# MTRduino_Rev2_1.net
KiCad netlist of a schematic drawn in EAGLE
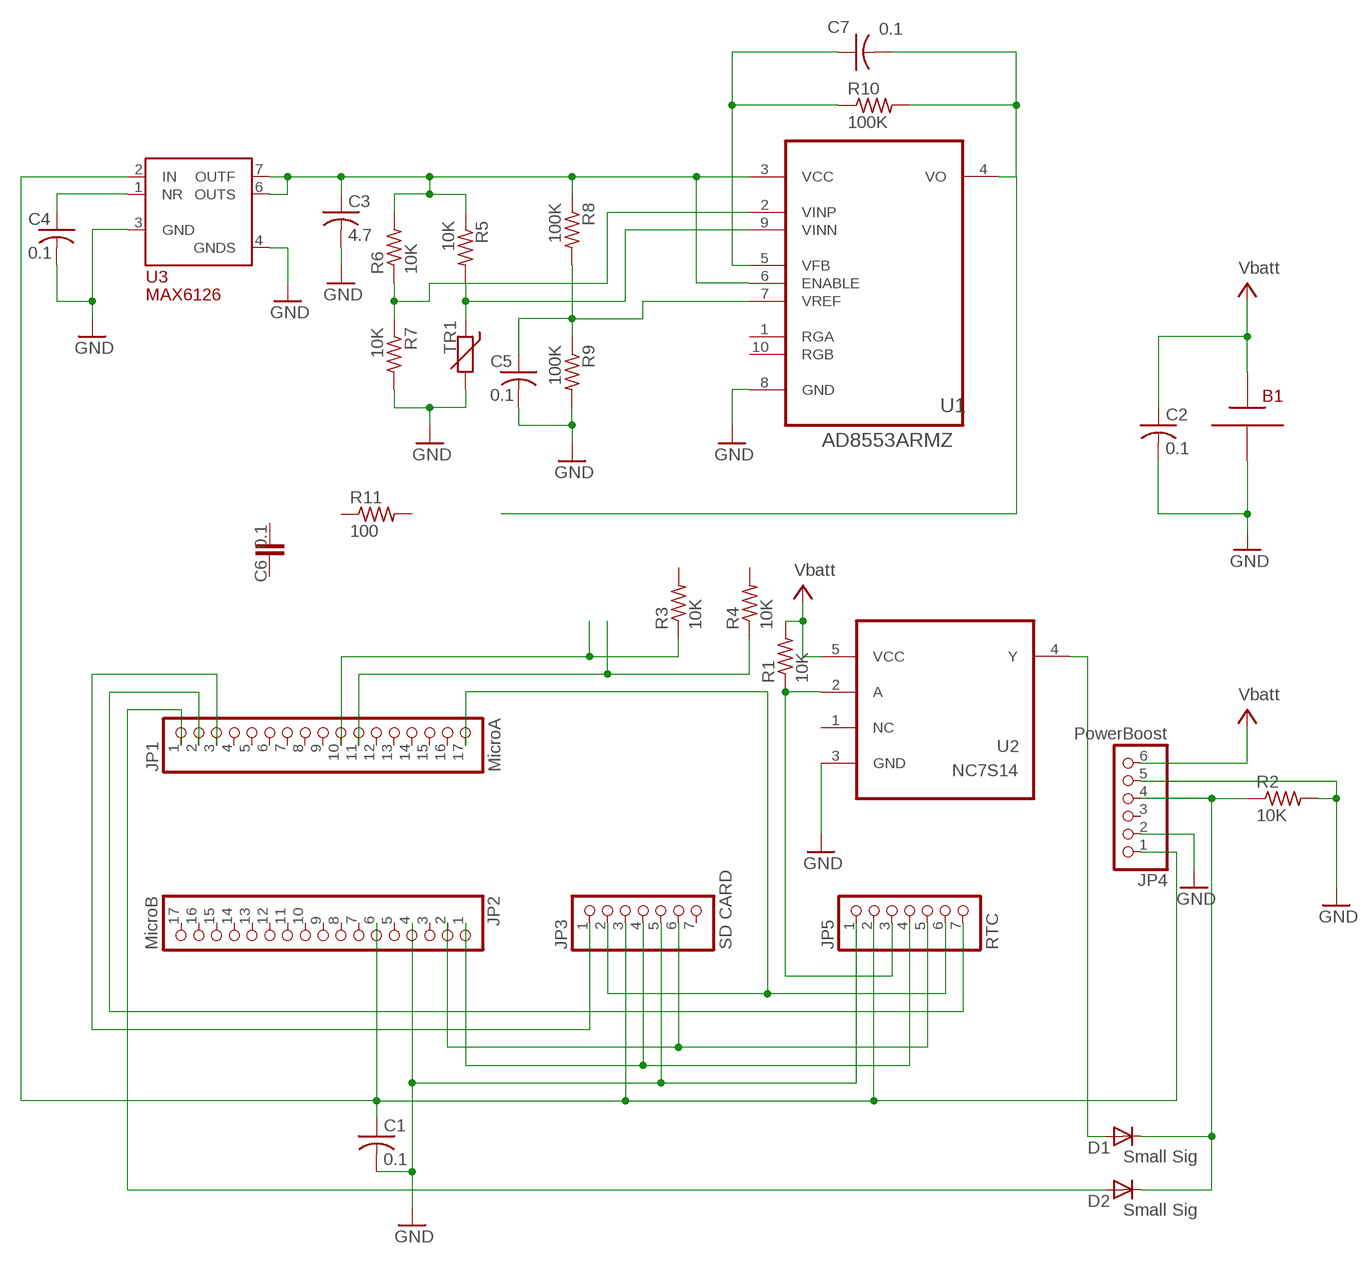
[diagram p0: schematic, sheet 1]

(export (version "E")
  (design (tool "Eeschema 10.0.6"))
  (components
    (comp (ref "B1")
      (value "2x AA BATT")
      (footprint "eagle-import:BATT_AA2")
      (libsource (lib "eagle-import") (part "BATT_AA2"))
    )
    (comp (ref "C1")
      (value "0.1")
      (footprint "eagle-import:C0603")
      (libsource (lib "eagle-import") (part "C-USC0603"))
    )
    (comp (ref "C2")
      (value "0.1")
      (footprint "eagle-import:C0603")
      (libsource (lib "eagle-import") (part "C-USC0603"))
    )
    (comp (ref "C3")
      (value "4.7")
      (footprint "eagle-import:C0603")
      (libsource (lib "eagle-import") (part "C-USC0603"))
    )
    (comp (ref "C4")
      (value "0.1")
      (footprint "eagle-import:C0603")
      (libsource (lib "eagle-import") (part "C-USC0603"))
    )
    (comp (ref "C5")
      (value "0.1")
      (footprint "eagle-import:C0603")
      (libsource (lib "eagle-import") (part "C-USC0603"))
    )
    (comp (ref "C6")
      (value "0.1")
      (footprint "eagle-import:C0603")
      (libsource (lib "eagle-import") (part "C-EUC0603"))
    )
    (comp (ref "C7")
      (value "0.1")
      (footprint "eagle-import:C0603")
      (libsource (lib "eagle-import") (part "C-USC0603"))
    )
    (comp (ref "D1")
      (value "Small Sig")
      (footprint "eagle-import:SOD-323F")
      (libsource (lib "eagle-import") (part "DIODESOD-323F"))
    )
    (comp (ref "D2")
      (value "Small Sig")
      (footprint "eagle-import:SOD-323F")
      (libsource (lib "eagle-import") (part "DIODESOD-323F"))
    )
    (comp (ref "JP1")
      (value "MicroA")
      (footprint "eagle-import:1X17")
      (libsource (lib "eagle-import") (part "PINHD-1X17"))
    )
    (comp (ref "JP2")
      (value "MicroB")
      (footprint "eagle-import:1X17")
      (libsource (lib "eagle-import") (part "PINHD-1X17"))
    )
    (comp (ref "JP3")
      (value "SD CARD")
      (footprint "eagle-import:1X07")
      (libsource (lib "eagle-import") (part "PINHD-1X7"))
    )
    (comp (ref "JP4")
      (value "PowerBoost")
      (footprint "eagle-import:1X06")
      (libsource (lib "eagle-import") (part "PINHD-1X6"))
    )
    (comp (ref "JP5")
      (value "RTC")
      (footprint "eagle-import:1X07")
      (libsource (lib "eagle-import") (part "PINHD-1X7"))
    )
    (comp (ref "R1")
      (value "10K")
      (footprint "eagle-import:R0603")
      (libsource (lib "eagle-import") (part "R-US_R0603"))
    )
    (comp (ref "R2")
      (value "10K")
      (footprint "eagle-import:R0603")
      (libsource (lib "eagle-import") (part "R-US_R0603"))
    )
    (comp (ref "R3")
      (value "10K")
      (footprint "eagle-import:R0603")
      (libsource (lib "eagle-import") (part "R-US_R0603"))
    )
    (comp (ref "R4")
      (value "10K")
      (footprint "eagle-import:R0603")
      (libsource (lib "eagle-import") (part "R-US_R0603"))
    )
    (comp (ref "R5")
      (value "10K")
      (footprint "eagle-import:R0603")
      (libsource (lib "eagle-import") (part "R-US_R0603"))
    )
    (comp (ref "R6")
      (value "10K")
      (footprint "eagle-import:R0603")
      (libsource (lib "eagle-import") (part "R-US_R0603"))
    )
    (comp (ref "R7")
      (value "10K")
      (footprint "eagle-import:R0603")
      (libsource (lib "eagle-import") (part "R-US_R0603"))
    )
    (comp (ref "R8")
      (value "100K")
      (footprint "eagle-import:R0603")
      (libsource (lib "eagle-import") (part "R-US_R0603"))
    )
    (comp (ref "R9")
      (value "100K")
      (footprint "eagle-import:R0603")
      (libsource (lib "eagle-import") (part "R-US_R0603"))
    )
    (comp (ref "R10")
      (value "100K")
      (footprint "eagle-import:R0603")
      (libsource (lib "eagle-import") (part "R-US_R0603"))
    )
    (comp (ref "R11")
      (value "100")
      (footprint "eagle-import:R0603")
      (libsource (lib "eagle-import") (part "R-US_R0603"))
    )
    (comp (ref "TR1")
      (value "10K")
      (footprint "eagle-import:R-5")
      (libsource (lib "eagle-import") (part "THERMISTOR_R-5"))
    )
    (comp (ref "U1")
      (value "AD8553ARMZ")
      (footprint "eagle-import:SOP50P490X110-10N")
      (libsource (lib "eagle-import") (part "AD8553ARMZ"))
    )
    (comp (ref "U2")
      (value "NC7S14")
      (footprint "eagle-import:SOT95P280X145-5N")
      (fields (field (name "MPN") "1P1G14MDBVREPG4"))
      (libsource (lib "eagle-import") (part "1P1G14MDBVREPG4"))
    )
    (comp (ref "U3")
      (value "MAX6126")
      (footprint "eagle-import:SOIC127P600X175-8N")
      (libsource (lib "eagle-import") (part "MAX6126"))
    )
  )
  (nets
    (net (code "1") (name "GND") (class "Default")
      (node (ref "B1") (pin "-") (pinfunction "-_-") (pintype "bidirectional"))
      (node (ref "C1") (pin "2") (pinfunction "2_2") (pintype "passive"))
      (node (ref "C2") (pin "2") (pinfunction "2_2") (pintype "passive"))
      (node (ref "C3") (pin "2") (pinfunction "2_2") (pintype "passive"))
      (node (ref "C4") (pin "2") (pinfunction "2_2") (pintype "passive"))
      (node (ref "C5") (pin "2") (pinfunction "2_2") (pintype "passive"))
      (node (ref "JP2") (pin "4") (pinfunction "4_4") (pintype "passive"))
      (node (ref "JP3") (pin "5") (pinfunction "5_5") (pintype "passive"))
      (node (ref "JP4") (pin "2") (pinfunction "2_2") (pintype "passive"))
      (node (ref "JP4") (pin "5") (pinfunction "5_5") (pintype "passive"))
      (node (ref "JP5") (pin "1") (pinfunction "1_1") (pintype "passive"))
      (node (ref "R2") (pin "2") (pinfunction "2_2") (pintype "passive"))
      (node (ref "R7") (pin "2") (pinfunction "2_2") (pintype "passive"))
      (node (ref "R9") (pin "2") (pinfunction "2_2") (pintype "passive"))
      (node (ref "TR1") (pin "2") (pinfunction "2_2") (pintype "passive"))
      (node (ref "U1") (pin "8") (pinfunction "GND_8") (pintype "passive"))
      (node (ref "U2") (pin "3") (pinfunction "GND_3") (pintype "passive"))
      (node (ref "U3") (pin "3") (pinfunction "GND_3") (pintype "input"))
      (node (ref "U3") (pin "4") (pinfunction "GNDS_4") (pintype "input"))
    )
    (net (code "2") (name "Net-(D1-PadC)") (class "Default")
      (node (ref "D1") (pin "C") (pinfunction "C_C") (pintype "passive"))
      (node (ref "D2") (pin "C") (pinfunction "C_C") (pintype "passive"))
      (node (ref "JP4") (pin "4") (pinfunction "4_4") (pintype "passive"))
      (node (ref "R2") (pin "1") (pinfunction "1_1") (pintype "passive"))
    )
    (net (code "3") (name "Net-(D2-PadA)") (class "Default")
      (node (ref "D2") (pin "A") (pinfunction "A_A") (pintype "passive"))
      (node (ref "JP1") (pin "1") (pinfunction "1_1") (pintype "passive"))
    )
    (net (code "4") (name "Net-(JP1-Pad2)") (class "Default")
      (node (ref "JP1") (pin "2") (pinfunction "2_2") (pintype "passive"))
      (node (ref "JP5") (pin "7") (pinfunction "7_7") (pintype "passive"))
    )
    (net (code "5") (name "Net-(JP1-Pad3)") (class "Default")
      (node (ref "JP1") (pin "3") (pinfunction "3_3") (pintype "passive"))
      (node (ref "JP3") (pin "1") (pinfunction "1_1") (pintype "passive"))
    )
    (net (code "6") (name "Net-(JP1-Pad10)") (class "Default")
      (node (ref "JP1") (pin "10") (pinfunction "10_10") (pintype "passive"))
      (node (ref "R3") (pin "1") (pinfunction "1_1") (pintype "passive"))
    )
    (net (code "7") (name "Net-(JP1-Pad11)") (class "Default")
      (node (ref "JP1") (pin "11") (pinfunction "11_11") (pintype "passive"))
      (node (ref "R4") (pin "1") (pinfunction "1_1") (pintype "passive"))
    )
    (net (code "8") (name "Net-(JP1-Pad17)") (class "Default")
      (node (ref "JP1") (pin "17") (pinfunction "17_17") (pintype "passive"))
      (node (ref "JP3") (pin "2") (pinfunction "2_2") (pintype "passive"))
      (node (ref "JP5") (pin "6") (pinfunction "6_6") (pintype "passive"))
    )
    (net (code "9") (name "Net-(JP2-Pad1)") (class "Default")
      (node (ref "JP2") (pin "1") (pinfunction "1_1") (pintype "passive"))
      (node (ref "JP3") (pin "4") (pinfunction "4_4") (pintype "passive"))
      (node (ref "JP5") (pin "4") (pinfunction "4_4") (pintype "passive"))
    )
    (net (code "10") (name "Net-(JP2-Pad2)") (class "Default")
      (node (ref "JP2") (pin "2") (pinfunction "2_2") (pintype "passive"))
      (node (ref "JP3") (pin "6") (pinfunction "6_6") (pintype "passive"))
      (node (ref "JP5") (pin "5") (pinfunction "5_5") (pintype "passive"))
    )
    (net (code "11") (name "Net-(U1-ENABLE)") (class "Default")
      (node (ref "C3") (pin "1") (pinfunction "1_1") (pintype "passive"))
      (node (ref "R5") (pin "1") (pinfunction "1_1") (pintype "passive"))
      (node (ref "R6") (pin "2") (pinfunction "2_2") (pintype "passive"))
      (node (ref "R8") (pin "1") (pinfunction "1_1") (pintype "passive"))
      (node (ref "U1") (pin "3") (pinfunction "VCC_3") (pintype "power_in"))
      (node (ref "U1") (pin "6") (pinfunction "ENABLE_6") (pintype "input"))
      (node (ref "U3") (pin "6") (pinfunction "OUTS_6") (pintype "output"))
      (node (ref "U3") (pin "7") (pinfunction "OUTF_7") (pintype "output"))
    )
    (net (code "12") (name "Net-(U1-VFB)") (class "Default")
      (node (ref "C7") (pin "1") (pinfunction "1_1") (pintype "passive"))
      (node (ref "R10") (pin "1") (pinfunction "1_1") (pintype "passive"))
      (node (ref "U1") (pin "5") (pinfunction "VFB_5") (pintype "input"))
    )
    (net (code "13") (name "Net-(U1-VINN)") (class "Default")
      (node (ref "R5") (pin "2") (pinfunction "2_2") (pintype "passive"))
      (node (ref "TR1") (pin "1") (pinfunction "1_1") (pintype "passive"))
      (node (ref "U1") (pin "9") (pinfunction "VINN_9") (pintype "input"))
    )
    (net (code "14") (name "Net-(U1-VINP)") (class "Default")
      (node (ref "R6") (pin "1") (pinfunction "1_1") (pintype "passive"))
      (node (ref "R7") (pin "1") (pinfunction "1_1") (pintype "passive"))
      (node (ref "U1") (pin "2") (pinfunction "VINP_2") (pintype "input"))
    )
    (net (code "15") (name "Net-(U1-VO)") (class "Default")
      (node (ref "C7") (pin "2") (pinfunction "2_2") (pintype "passive"))
      (node (ref "R10") (pin "2") (pinfunction "2_2") (pintype "passive"))
      (node (ref "U1") (pin "4") (pinfunction "VO_4") (pintype "output"))
    )
    (net (code "16") (name "Net-(U1-VREF)") (class "Default")
      (node (ref "C5") (pin "1") (pinfunction "1_1") (pintype "passive"))
      (node (ref "R8") (pin "2") (pinfunction "2_2") (pintype "passive"))
      (node (ref "R9") (pin "1") (pinfunction "1_1") (pintype "passive"))
      (node (ref "U1") (pin "7") (pinfunction "VREF_7") (pintype "input"))
    )
    (net (code "17") (name "Net-(U2-A)") (class "Default")
      (node (ref "JP5") (pin "3") (pinfunction "3_3") (pintype "passive"))
      (node (ref "R1") (pin "1") (pinfunction "1_1") (pintype "passive"))
      (node (ref "U2") (pin "2") (pinfunction "A_2") (pintype "input"))
    )
    (net (code "18") (name "Net-(U2-Y)") (class "Default")
      (node (ref "D1") (pin "A") (pinfunction "A_A") (pintype "passive"))
      (node (ref "U2") (pin "4") (pinfunction "Y_4") (pintype "output"))
    )
    (net (code "19") (name "Net-(U3-IN)") (class "Default")
      (node (ref "C1") (pin "1") (pinfunction "1_1") (pintype "passive"))
      (node (ref "JP2") (pin "6") (pinfunction "6_6") (pintype "passive"))
      (node (ref "JP3") (pin "3") (pinfunction "3_3") (pintype "passive"))
      (node (ref "JP4") (pin "1") (pinfunction "1_1") (pintype "passive"))
      (node (ref "JP5") (pin "2") (pinfunction "2_2") (pintype "passive"))
      (node (ref "U3") (pin "2") (pinfunction "IN_2") (pintype "input"))
    )
    (net (code "20") (name "Net-(U3-NR)") (class "Default")
      (node (ref "C4") (pin "1") (pinfunction "1_1") (pintype "passive"))
      (node (ref "U3") (pin "1") (pinfunction "NR_1") (pintype "bidirectional"))
    )
    (net (code "21") (name "Vbatt") (class "Default")
      (node (ref "B1") (pin "+") (pinfunction "+_+") (pintype "bidirectional"))
      (node (ref "C2") (pin "1") (pinfunction "1_1") (pintype "passive"))
      (node (ref "JP4") (pin "6") (pinfunction "6_6") (pintype "passive"))
      (node (ref "R1") (pin "2") (pinfunction "2_2") (pintype "passive"))
      (node (ref "U2") (pin "5") (pinfunction "VCC_5") (pintype "power_in"))
    )
    (net (code "22") (name "unconnected-(C6-Pad1)") (class "Default")
      (node (ref "C6") (pin "1") (pinfunction "1_1") (pintype "passive"))
    )
    (net (code "23") (name "unconnected-(C6-Pad2)") (class "Default")
      (node (ref "C6") (pin "2") (pinfunction "2_2") (pintype "passive"))
    )
    (net (code "24") (name "unconnected-(JP1-Pad4)") (class "Default")
      (node (ref "JP1") (pin "4") (pinfunction "4_4") (pintype "passive"))
    )
    (net (code "25") (name "unconnected-(JP1-Pad5)") (class "Default")
      (node (ref "JP1") (pin "5") (pinfunction "5_5") (pintype "passive"))
    )
    (net (code "26") (name "unconnected-(JP1-Pad6)") (class "Default")
      (node (ref "JP1") (pin "6") (pinfunction "6_6") (pintype "passive"))
    )
    (net (code "27") (name "unconnected-(JP1-Pad7)") (class "Default")
      (node (ref "JP1") (pin "7") (pinfunction "7_7") (pintype "passive"))
    )
    (net (code "28") (name "unconnected-(JP1-Pad8)") (class "Default")
      (node (ref "JP1") (pin "8") (pinfunction "8_8") (pintype "passive"))
    )
    (net (code "29") (name "unconnected-(JP1-Pad9)") (class "Default")
      (node (ref "JP1") (pin "9") (pinfunction "9_9") (pintype "passive"))
    )
    (net (code "30") (name "unconnected-(JP1-Pad12)") (class "Default")
      (node (ref "JP1") (pin "12") (pinfunction "12_12") (pintype "passive"))
    )
    (net (code "31") (name "unconnected-(JP1-Pad13)") (class "Default")
      (node (ref "JP1") (pin "13") (pinfunction "13_13") (pintype "passive"))
    )
    (net (code "32") (name "unconnected-(JP1-Pad14)") (class "Default")
      (node (ref "JP1") (pin "14") (pinfunction "14_14") (pintype "passive"))
    )
    (net (code "33") (name "unconnected-(JP1-Pad15)") (class "Default")
      (node (ref "JP1") (pin "15") (pinfunction "15_15") (pintype "passive"))
    )
    (net (code "34") (name "unconnected-(JP1-Pad16)") (class "Default")
      (node (ref "JP1") (pin "16") (pinfunction "16_16") (pintype "passive"))
    )
    (net (code "35") (name "unconnected-(JP2-Pad3)") (class "Default")
      (node (ref "JP2") (pin "3") (pinfunction "3_3") (pintype "passive"))
    )
    (net (code "36") (name "unconnected-(JP2-Pad5)") (class "Default")
      (node (ref "JP2") (pin "5") (pinfunction "5_5") (pintype "passive"))
    )
    (net (code "37") (name "unconnected-(JP2-Pad7)") (class "Default")
      (node (ref "JP2") (pin "7") (pinfunction "7_7") (pintype "passive"))
    )
    (net (code "38") (name "unconnected-(JP2-Pad8)") (class "Default")
      (node (ref "JP2") (pin "8") (pinfunction "8_8") (pintype "passive"))
    )
    (net (code "39") (name "unconnected-(JP2-Pad9)") (class "Default")
      (node (ref "JP2") (pin "9") (pinfunction "9_9") (pintype "passive"))
    )
    (net (code "40") (name "unconnected-(JP2-Pad10)") (class "Default")
      (node (ref "JP2") (pin "10") (pinfunction "10_10") (pintype "passive"))
    )
    (net (code "41") (name "unconnected-(JP2-Pad11)") (class "Default")
      (node (ref "JP2") (pin "11") (pinfunction "11_11") (pintype "passive"))
    )
    (net (code "42") (name "unconnected-(JP2-Pad12)") (class "Default")
      (node (ref "JP2") (pin "12") (pinfunction "12_12") (pintype "passive"))
    )
    (net (code "43") (name "unconnected-(JP2-Pad13)") (class "Default")
      (node (ref "JP2") (pin "13") (pinfunction "13_13") (pintype "passive"))
    )
    (net (code "44") (name "unconnected-(JP2-Pad14)") (class "Default")
      (node (ref "JP2") (pin "14") (pinfunction "14_14") (pintype "passive"))
    )
    (net (code "45") (name "unconnected-(JP2-Pad15)") (class "Default")
      (node (ref "JP2") (pin "15") (pinfunction "15_15") (pintype "passive"))
    )
    (net (code "46") (name "unconnected-(JP2-Pad16)") (class "Default")
      (node (ref "JP2") (pin "16") (pinfunction "16_16") (pintype "passive"))
    )
    (net (code "47") (name "unconnected-(JP2-Pad17)") (class "Default")
      (node (ref "JP2") (pin "17") (pinfunction "17_17") (pintype "passive"))
    )
    (net (code "48") (name "unconnected-(JP3-Pad7)") (class "Default")
      (node (ref "JP3") (pin "7") (pinfunction "7_7") (pintype "passive"))
    )
    (net (code "49") (name "unconnected-(JP4-Pad3)") (class "Default")
      (node (ref "JP4") (pin "3") (pinfunction "3_3") (pintype "passive"))
    )
    (net (code "50") (name "unconnected-(R3-Pad2)") (class "Default")
      (node (ref "R3") (pin "2") (pinfunction "2_2") (pintype "passive"))
    )
    (net (code "51") (name "unconnected-(R4-Pad2)") (class "Default")
      (node (ref "R4") (pin "2") (pinfunction "2_2") (pintype "passive"))
    )
    (net (code "52") (name "unconnected-(R11-Pad1)") (class "Default")
      (node (ref "R11") (pin "1") (pinfunction "1_1") (pintype "passive"))
    )
    (net (code "53") (name "unconnected-(R11-Pad2)") (class "Default")
      (node (ref "R11") (pin "2") (pinfunction "2_2") (pintype "passive"))
    )
    (net (code "54") (name "unconnected-(U1-RGA-Pad1)") (class "Default")
      (node (ref "U1") (pin "1") (pinfunction "RGA_1") (pintype "passive"))
    )
    (net (code "55") (name "unconnected-(U1-RGB-Pad10)") (class "Default")
      (node (ref "U1") (pin "10") (pinfunction "RGB_10") (pintype "passive"))
    )
    (net (code "56") (name "unconnected-(U2-NC-Pad1)") (class "Default")
      (node (ref "U2") (pin "1") (pinfunction "NC_1") (pintype "no_connect"))
    )
  )
)
